# 1_NZPP.net
KiCad netlist of a schematic drawn in Altium Designer
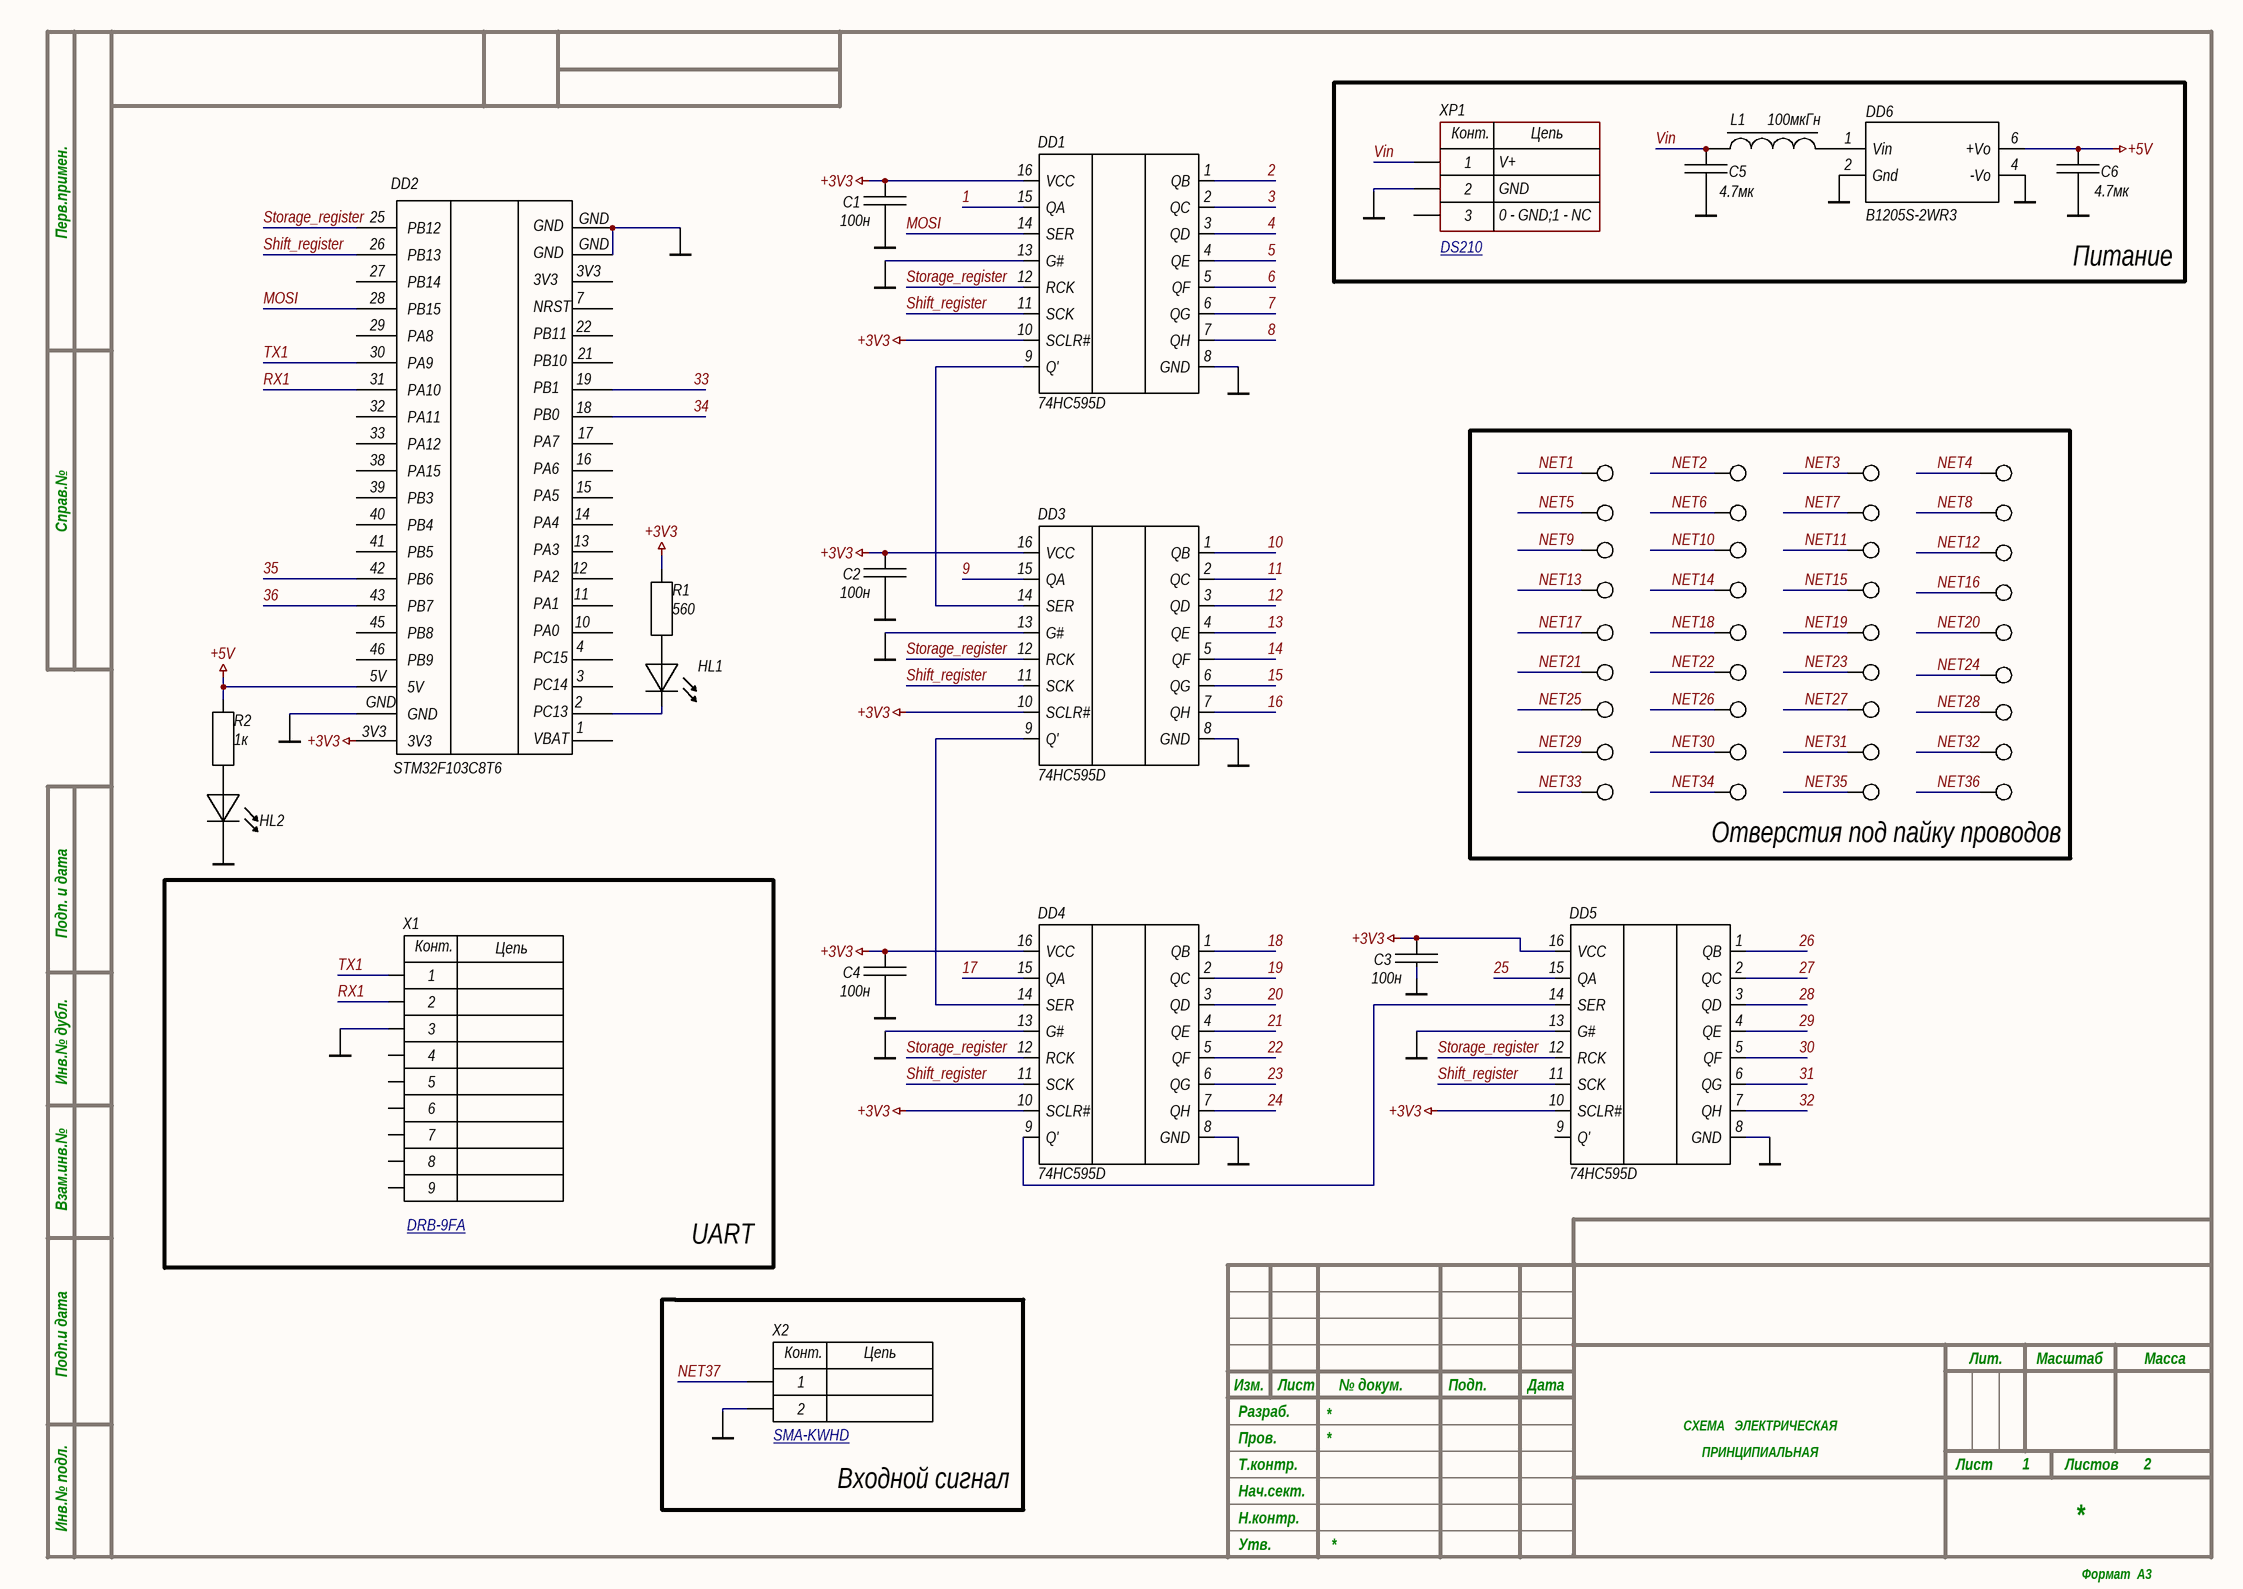
[diagram p0: 1.NZPP.SchDoc]

(export (version "E")
  (design (tool "Eeschema 10.0.6"))
  (components
    (comp (ref "*") (value "Point") (footprint "Point") (libsource (lib "Schlib1") (part "Point")))
    (comp (ref "*1") (value "Point") (footprint "Point") (libsource (lib "Schlib1") (part "Point")))
    (comp (ref "*2") (value "Point") (footprint "Point") (libsource (lib "Schlib1") (part "Point")))
    (comp (ref "*3") (value "Point") (footprint "Point") (libsource (lib "Schlib1") (part "Point")))
    (comp (ref "*4") (value "Point") (footprint "Point") (libsource (lib "Schlib1") (part "Point")))
    (comp (ref "*5") (value "Point") (footprint "Point") (libsource (lib "Schlib1") (part "Point")))
    (comp (ref "*6") (value "Point") (footprint "Point") (libsource (lib "Schlib1") (part "Point")))
    (comp (ref "*7") (value "Point") (footprint "Point") (libsource (lib "Schlib1") (part "Point")))
    (comp (ref "*8") (value "Point") (footprint "Point") (libsource (lib "Schlib1") (part "Point")))
    (comp (ref "*9") (value "Point") (footprint "Point") (libsource (lib "Schlib1") (part "Point")))
    (comp (ref "*10") (value "Point") (footprint "Point") (libsource (lib "Schlib1") (part "Point")))
    (comp (ref "*11") (value "Point") (footprint "Point") (libsource (lib "Schlib1") (part "Point")))
    (comp (ref "*12") (value "Point") (footprint "Point") (libsource (lib "Schlib1") (part "Point")))
    (comp (ref "*13") (value "Point") (footprint "Point") (libsource (lib "Schlib1") (part "Point")))
    (comp (ref "*14") (value "Point") (footprint "Point") (libsource (lib "Schlib1") (part "Point")))
    (comp (ref "*15") (value "Point") (footprint "Point") (libsource (lib "Schlib1") (part "Point")))
    (comp (ref "*16") (value "Point") (footprint "Point") (libsource (lib "Schlib1") (part "Point")))
    (comp (ref "*17") (value "Point") (footprint "Point") (libsource (lib "Schlib1") (part "Point")))
    (comp (ref "*18") (value "Point") (footprint "Point") (libsource (lib "Schlib1") (part "Point")))
    (comp (ref "*19") (value "Point") (footprint "Point") (libsource (lib "Schlib1") (part "Point")))
    (comp (ref "*20") (value "Point") (footprint "Point") (libsource (lib "Schlib1") (part "Point")))
    (comp (ref "*21") (value "Point") (footprint "Point") (libsource (lib "Schlib1") (part "Point")))
    (comp (ref "*22") (value "Point") (footprint "Point") (libsource (lib "Schlib1") (part "Point")))
    (comp (ref "*23") (value "Point") (footprint "Point") (libsource (lib "Schlib1") (part "Point")))
    (comp (ref "*24") (value "Point") (footprint "Point") (libsource (lib "Schlib1") (part "Point")))
    (comp (ref "*25") (value "Point") (footprint "Point") (libsource (lib "Schlib1") (part "Point")))
    (comp (ref "*26") (value "Point") (footprint "Point") (libsource (lib "Schlib1") (part "Point")))
    (comp (ref "*27") (value "Point") (footprint "Point") (libsource (lib "Schlib1") (part "Point")))
    (comp (ref "*28") (value "Point") (footprint "Point") (libsource (lib "Schlib1") (part "Point")))
    (comp (ref "*29") (value "Point") (footprint "Point") (libsource (lib "Schlib1") (part "Point")))
    (comp (ref "*30") (value "Point") (footprint "Point") (libsource (lib "Schlib1") (part "Point")))
    (comp (ref "*31") (value "Point") (footprint "Point") (libsource (lib "Schlib1") (part "Point")))
    (comp (ref "*32") (value "Point") (footprint "Point") (libsource (lib "Schlib1") (part "Point")))
    (comp (ref "*33") (value "Point") (footprint "Point") (libsource (lib "Schlib1") (part "Point")))
    (comp (ref "*34") (value "Point") (footprint "Point") (libsource (lib "Schlib1") (part "Point")))
    (comp (ref "*35") (value "Point") (footprint "Point") (libsource (lib "Schlib1") (part "Point")))
    (comp (ref "C1")
      (value "100н")
      (footprint "CAP: 0805")
      (libsource (lib "capacitor") (part "Ceramic_0805"))
    )
    (comp (ref "C2")
      (value "100н")
      (footprint "CAP: 0805")
      (libsource (lib "capacitor") (part "Ceramic_0805"))
    )
    (comp (ref "C3")
      (value "100н")
      (footprint "CAP: 0805")
      (libsource (lib "capacitor") (part "Ceramic_0805"))
    )
    (comp (ref "C4")
      (value "100н")
      (footprint "CAP: 0805")
      (libsource (lib "capacitor") (part "Ceramic_0805"))
    )
    (comp (ref "C5")
      (value "4.7мк")
      (footprint "CAP: 0805")
      (libsource (lib "capacitor") (part "Ceramic_0805"))
    )
    (comp (ref "C6")
      (value "4.7мк")
      (footprint "CAP: 0805")
      (libsource (lib "capacitor") (part "Ceramic_0805"))
    )
    (comp (ref "DD1") (value "74HC595D") (footprint "74HC595D") (libsource (lib "Schlib1") (part "74HC595D")))
    (comp (ref "DD2")
      (value "STM32F103C8T6")
      (footprint "STM32F103C8T6 - duplicate")
      (libsource (lib "Schlib1") (part "STM32F103"))
    )
    (comp (ref "DD3") (value "74HC595D") (footprint "74HC595D") (libsource (lib "") (part "74HC595D_1")))
    (comp (ref "DD4") (value "74HC595D") (footprint "74HC595D") (libsource (lib "") (part "74HC595D_1")))
    (comp (ref "DD5") (value "74HC595D") (footprint "74HC595D") (libsource (lib "") (part "74HC595D_1")))
    (comp (ref "DD6")
      (value "B1205S-2WR3")
      (footprint "B1205S-2WR3")
      (libsource (lib "Schlib1") (part "B1205S-2WR3"))
    )
    (comp (ref "HL1") (value "GNL-3012HD") (footprint "led green") (libsource (lib "Schlib1") (part "LED")))
    (comp (ref "HL2") (value "GNL-3012HD") (footprint "led") (libsource (lib "Schlib1") (part "LED")))
    (comp (ref "L1")
      (value "100мкГн")
      (footprint "100мкГн")
      (libsource (lib "Schlib1") (part "Дроссель 100мкГн CD43-101K"))
    )
    (comp (ref "R1")
      (value "560")
      (footprint "RES: 0805")
      (libsource (lib "resistor") (part "Resistor_0805"))
    )
    (comp (ref "R2") (value "1к") (footprint "RES: 0805") (libsource (lib "resistor") (part "Resistor_0805")))
    (comp (ref "X1") (value "DRB-9FA") (footprint "CON: DB-9F") (libsource (lib "Schlib1") (part "DRB-9FA")))
    (comp (ref "X2")
      (value "SMA-KWHD")
      (footprint "CON: SMA-KWHD")
      (libsource (lib "Schlib1") (part "Connector_terminal_2pin"))
    )
    (comp (ref "XP1") (value "DS210") (footprint "CON: DS210") (libsource (lib "Schlib1") (part "DS210")))
  )
  (nets
    (net (code "1") (name "+3V3") (class "Default")
      (node (ref "C1") (pin "2") (pinfunction "2_2") (pintype "passive"))
      (node (ref "C2") (pin "2") (pinfunction "2_2") (pintype "passive"))
      (node (ref "C3") (pin "2") (pinfunction "2_2") (pintype "passive"))
      (node (ref "C4") (pin "2") (pinfunction "2_2") (pintype "passive"))
      (node (ref "DD1") (pin "10") (pinfunction "SCLR#_10") (pintype "passive"))
      (node (ref "DD1") (pin "16") (pinfunction "VCC_16") (pintype "passive"))
      (node (ref "DD2") (pin "A2") (pinfunction "3V3_A2") (pintype "passive"))
      (node (ref "DD3") (pin "10") (pinfunction "SCLR#_10") (pintype "passive"))
      (node (ref "DD3") (pin "16") (pinfunction "VCC_16") (pintype "passive"))
      (node (ref "DD4") (pin "10") (pinfunction "SCLR#_10") (pintype "passive"))
      (node (ref "DD4") (pin "16") (pinfunction "VCC_16") (pintype "passive"))
      (node (ref "DD5") (pin "10") (pinfunction "SCLR#_10") (pintype "passive"))
      (node (ref "DD5") (pin "16") (pinfunction "VCC_16") (pintype "passive"))
      (node (ref "R1") (pin "2") (pinfunction "2_2") (pintype "passive"))
    )
    (net (code "2") (name "+5V") (class "Default")
      (node (ref "C6") (pin "2") (pinfunction "2_2") (pintype "passive"))
      (node (ref "DD2") (pin "5V") (pinfunction "5V_5V") (pintype "passive"))
      (node (ref "DD6") (pin "6") (pinfunction "+Vo_6") (pintype "passive"))
      (node (ref "R2") (pin "2") (pinfunction "2_2") (pintype "passive"))
    )
    (net (code "3") (name "/1") (class "Default")
      (node (ref "DD1") (pin "15") (pinfunction "QA_15") (pintype "passive"))
    )
    (net (code "4") (name "/2") (class "Default")
      (node (ref "DD1") (pin "1") (pinfunction "QB_1") (pintype "passive"))
    )
    (net (code "5") (name "/3") (class "Default")
      (node (ref "DD1") (pin "2") (pinfunction "QC_2") (pintype "passive"))
    )
    (net (code "6") (name "/4") (class "Default")
      (node (ref "DD1") (pin "3") (pinfunction "QD_3") (pintype "passive"))
    )
    (net (code "7") (name "/5") (class "Default")
      (node (ref "DD1") (pin "4") (pinfunction "QE_4") (pintype "passive"))
    )
    (net (code "8") (name "/6") (class "Default")
      (node (ref "DD1") (pin "5") (pinfunction "QF_5") (pintype "passive"))
    )
    (net (code "9") (name "/7") (class "Default")
      (node (ref "DD1") (pin "6") (pinfunction "QG_6") (pintype "passive"))
    )
    (net (code "10") (name "/8") (class "Default")
      (node (ref "DD1") (pin "7") (pinfunction "QH_7") (pintype "passive"))
    )
    (net (code "11") (name "/9") (class "Default")
      (node (ref "DD3") (pin "15") (pinfunction "QA_15") (pintype "passive"))
    )
    (net (code "12") (name "/10") (class "Default")
      (node (ref "DD3") (pin "1") (pinfunction "QB_1") (pintype "passive"))
    )
    (net (code "13") (name "/11") (class "Default")
      (node (ref "DD3") (pin "2") (pinfunction "QC_2") (pintype "passive"))
    )
    (net (code "14") (name "/12") (class "Default")
      (node (ref "DD3") (pin "3") (pinfunction "QD_3") (pintype "passive"))
    )
    (net (code "15") (name "/13") (class "Default")
      (node (ref "DD3") (pin "4") (pinfunction "QE_4") (pintype "passive"))
    )
    (net (code "16") (name "/14") (class "Default")
      (node (ref "DD3") (pin "5") (pinfunction "QF_5") (pintype "passive"))
    )
    (net (code "17") (name "/15") (class "Default")
      (node (ref "DD3") (pin "6") (pinfunction "QG_6") (pintype "passive"))
    )
    (net (code "18") (name "/16") (class "Default")
      (node (ref "DD3") (pin "7") (pinfunction "QH_7") (pintype "passive"))
    )
    (net (code "19") (name "/17") (class "Default")
      (node (ref "DD4") (pin "15") (pinfunction "QA_15") (pintype "passive"))
    )
    (net (code "20") (name "/18") (class "Default")
      (node (ref "DD4") (pin "1") (pinfunction "QB_1") (pintype "passive"))
    )
    (net (code "21") (name "/19") (class "Default")
      (node (ref "DD4") (pin "2") (pinfunction "QC_2") (pintype "passive"))
    )
    (net (code "22") (name "/20") (class "Default")
      (node (ref "DD4") (pin "3") (pinfunction "QD_3") (pintype "passive"))
    )
    (net (code "23") (name "/21") (class "Default")
      (node (ref "DD4") (pin "4") (pinfunction "QE_4") (pintype "passive"))
    )
    (net (code "24") (name "/22") (class "Default")
      (node (ref "DD4") (pin "5") (pinfunction "QF_5") (pintype "passive"))
    )
    (net (code "25") (name "/23") (class "Default")
      (node (ref "DD4") (pin "6") (pinfunction "QG_6") (pintype "passive"))
    )
    (net (code "26") (name "/24") (class "Default")
      (node (ref "DD4") (pin "7") (pinfunction "QH_7") (pintype "passive"))
    )
    (net (code "27") (name "/25") (class "Default")
      (node (ref "DD5") (pin "15") (pinfunction "QA_15") (pintype "passive"))
    )
    (net (code "28") (name "/26") (class "Default")
      (node (ref "DD5") (pin "1") (pinfunction "QB_1") (pintype "passive"))
    )
    (net (code "29") (name "/27") (class "Default")
      (node (ref "DD5") (pin "2") (pinfunction "QC_2") (pintype "passive"))
    )
    (net (code "30") (name "/28") (class "Default")
      (node (ref "DD5") (pin "3") (pinfunction "QD_3") (pintype "passive"))
    )
    (net (code "31") (name "/29") (class "Default")
      (node (ref "DD5") (pin "4") (pinfunction "QE_4") (pintype "passive"))
    )
    (net (code "32") (name "/30") (class "Default")
      (node (ref "DD5") (pin "5") (pinfunction "QF_5") (pintype "passive"))
    )
    (net (code "33") (name "/31") (class "Default")
      (node (ref "DD5") (pin "6") (pinfunction "QG_6") (pintype "passive"))
    )
    (net (code "34") (name "/32") (class "Default")
      (node (ref "DD5") (pin "7") (pinfunction "QH_7") (pintype "passive"))
    )
    (net (code "35") (name "/33") (class "Default")
      (node (ref "DD2") (pin "19") (pinfunction "PB1_19") (pintype "passive"))
    )
    (net (code "36") (name "/34") (class "Default")
      (node (ref "DD2") (pin "18") (pinfunction "PB0_18") (pintype "passive"))
    )
    (net (code "37") (name "/35") (class "Default")
      (node (ref "DD2") (pin "42") (pinfunction "PB6_42") (pintype "passive"))
    )
    (net (code "38") (name "/36") (class "Default")
      (node (ref "DD2") (pin "43") (pinfunction "PB7_43") (pintype "passive"))
    )
    (net (code "39") (name "/MOSI") (class "Default")
      (node (ref "DD1") (pin "14") (pinfunction "SER_14") (pintype "passive"))
      (node (ref "DD2") (pin "28") (pinfunction "PB15_28") (pintype "passive"))
    )
    (net (code "40") (name "/NET1") (class "Default")
      (node (ref "*") (pin "1") (pinfunction "4_1") (pintype "passive"))
    )
    (net (code "41") (name "/NET2") (class "Default")
      (node (ref "*1") (pin "1") (pinfunction "4_1") (pintype "passive"))
    )
    (net (code "42") (name "/NET3") (class "Default")
      (node (ref "*2") (pin "1") (pinfunction "4_1") (pintype "passive"))
    )
    (net (code "43") (name "/NET4") (class "Default")
      (node (ref "*3") (pin "1") (pinfunction "4_1") (pintype "passive"))
    )
    (net (code "44") (name "/NET5") (class "Default")
      (node (ref "*4") (pin "1") (pinfunction "4_1") (pintype "passive"))
    )
    (net (code "45") (name "/NET6") (class "Default")
      (node (ref "*5") (pin "1") (pinfunction "4_1") (pintype "passive"))
    )
    (net (code "46") (name "/NET7") (class "Default")
      (node (ref "*6") (pin "1") (pinfunction "4_1") (pintype "passive"))
    )
    (net (code "47") (name "/NET8") (class "Default")
      (node (ref "*7") (pin "1") (pinfunction "4_1") (pintype "passive"))
    )
    (net (code "48") (name "/NET9") (class "Default")
      (node (ref "*8") (pin "1") (pinfunction "4_1") (pintype "passive"))
    )
    (net (code "49") (name "/NET10") (class "Default")
      (node (ref "*9") (pin "1") (pinfunction "4_1") (pintype "passive"))
    )
    (net (code "50") (name "/NET11") (class "Default")
      (node (ref "*10") (pin "1") (pinfunction "4_1") (pintype "passive"))
    )
    (net (code "51") (name "/NET12") (class "Default")
      (node (ref "*11") (pin "1") (pinfunction "4_1") (pintype "passive"))
    )
    (net (code "52") (name "/NET13") (class "Default")
      (node (ref "*12") (pin "1") (pinfunction "4_1") (pintype "passive"))
    )
    (net (code "53") (name "/NET14") (class "Default")
      (node (ref "*13") (pin "1") (pinfunction "4_1") (pintype "passive"))
    )
    (net (code "54") (name "/NET15") (class "Default")
      (node (ref "*14") (pin "1") (pinfunction "4_1") (pintype "passive"))
    )
    (net (code "55") (name "/NET16") (class "Default")
      (node (ref "*15") (pin "1") (pinfunction "4_1") (pintype "passive"))
    )
    (net (code "56") (name "/NET17") (class "Default")
      (node (ref "*16") (pin "1") (pinfunction "4_1") (pintype "passive"))
    )
    (net (code "57") (name "/NET18") (class "Default")
      (node (ref "*17") (pin "1") (pinfunction "4_1") (pintype "passive"))
    )
    (net (code "58") (name "/NET19") (class "Default")
      (node (ref "*18") (pin "1") (pinfunction "4_1") (pintype "passive"))
    )
    (net (code "59") (name "/NET20") (class "Default")
      (node (ref "*19") (pin "1") (pinfunction "4_1") (pintype "passive"))
    )
    (net (code "60") (name "/NET21") (class "Default")
      (node (ref "*20") (pin "1") (pinfunction "4_1") (pintype "passive"))
    )
    (net (code "61") (name "/NET22") (class "Default")
      (node (ref "*21") (pin "1") (pinfunction "4_1") (pintype "passive"))
    )
    (net (code "62") (name "/NET23") (class "Default")
      (node (ref "*22") (pin "1") (pinfunction "4_1") (pintype "passive"))
    )
    (net (code "63") (name "/NET24") (class "Default")
      (node (ref "*23") (pin "1") (pinfunction "4_1") (pintype "passive"))
    )
    (net (code "64") (name "/NET25") (class "Default")
      (node (ref "*24") (pin "1") (pinfunction "4_1") (pintype "passive"))
    )
    (net (code "65") (name "/NET26") (class "Default")
      (node (ref "*25") (pin "1") (pinfunction "4_1") (pintype "passive"))
    )
    (net (code "66") (name "/NET27") (class "Default")
      (node (ref "*26") (pin "1") (pinfunction "4_1") (pintype "passive"))
    )
    (net (code "67") (name "/NET28") (class "Default")
      (node (ref "*27") (pin "1") (pinfunction "4_1") (pintype "passive"))
    )
    (net (code "68") (name "/NET29") (class "Default")
      (node (ref "*28") (pin "1") (pinfunction "4_1") (pintype "passive"))
    )
    (net (code "69") (name "/NET30") (class "Default")
      (node (ref "*29") (pin "1") (pinfunction "4_1") (pintype "passive"))
    )
    (net (code "70") (name "/NET31") (class "Default")
      (node (ref "*30") (pin "1") (pinfunction "4_1") (pintype "passive"))
    )
    (net (code "71") (name "/NET32") (class "Default")
      (node (ref "*31") (pin "1") (pinfunction "4_1") (pintype "passive"))
    )
    (net (code "72") (name "/NET33") (class "Default")
      (node (ref "*32") (pin "1") (pinfunction "4_1") (pintype "passive"))
    )
    (net (code "73") (name "/NET34") (class "Default")
      (node (ref "*33") (pin "1") (pinfunction "4_1") (pintype "passive"))
    )
    (net (code "74") (name "/NET35") (class "Default")
      (node (ref "*34") (pin "1") (pinfunction "4_1") (pintype "passive"))
    )
    (net (code "75") (name "/NET36") (class "Default")
      (node (ref "*35") (pin "1") (pinfunction "4_1") (pintype "passive"))
    )
    (net (code "76") (name "/NET37") (class "Default")
      (node (ref "X2") (pin "1") (pinfunction "1_1") (pintype "passive"))
    )
    (net (code "77") (name "/RX1") (class "Default")
      (node (ref "DD2") (pin "31") (pinfunction "PA10_31") (pintype "passive"))
      (node (ref "X1") (pin "2") (pinfunction "2_2") (pintype "passive"))
    )
    (net (code "78") (name "/Shift_register") (class "Default")
      (node (ref "DD1") (pin "11") (pinfunction "SCK_11") (pintype "passive"))
      (node (ref "DD2") (pin "26") (pinfunction "PB13_26") (pintype "passive"))
      (node (ref "DD3") (pin "11") (pinfunction "SCK_11") (pintype "passive"))
      (node (ref "DD4") (pin "11") (pinfunction "SCK_11") (pintype "passive"))
      (node (ref "DD5") (pin "11") (pinfunction "SCK_11") (pintype "passive"))
    )
    (net (code "79") (name "/Storage_register") (class "Default")
      (node (ref "DD1") (pin "12") (pinfunction "RCK_12") (pintype "passive"))
      (node (ref "DD2") (pin "25") (pinfunction "PB12_25") (pintype "passive"))
      (node (ref "DD3") (pin "12") (pinfunction "RCK_12") (pintype "passive"))
      (node (ref "DD4") (pin "12") (pinfunction "RCK_12") (pintype "passive"))
      (node (ref "DD5") (pin "12") (pinfunction "RCK_12") (pintype "passive"))
    )
    (net (code "80") (name "/TX1") (class "Default")
      (node (ref "DD2") (pin "30") (pinfunction "PA9_30") (pintype "passive"))
      (node (ref "X1") (pin "1") (pinfunction "1_1") (pintype "passive"))
    )
    (net (code "81") (name "/Vin") (class "Default")
      (node (ref "C5") (pin "2") (pinfunction "2_2") (pintype "passive"))
      (node (ref "L1") (pin "1") (pinfunction "1_1") (pintype "passive"))
      (node (ref "XP1") (pin "1") (pinfunction "1_1") (pintype "passive"))
    )
    (net (code "82") (name "GND") (class "Default")
      (node (ref "C1") (pin "1") (pinfunction "1_1") (pintype "passive"))
      (node (ref "C2") (pin "1") (pinfunction "1_1") (pintype "passive"))
      (node (ref "C3") (pin "1") (pinfunction "1_1") (pintype "passive"))
      (node (ref "C4") (pin "1") (pinfunction "1_1") (pintype "passive"))
      (node (ref "C5") (pin "1") (pinfunction "1_1") (pintype "passive"))
      (node (ref "C6") (pin "1") (pinfunction "1_1") (pintype "passive"))
      (node (ref "DD1") (pin "13") (pinfunction "G#_13") (pintype "passive"))
      (node (ref "DD1") (pin "8") (pinfunction "GND_8") (pintype "passive"))
      (node (ref "DD2") (pin "GND") (pinfunction "GND_GND") (pintype "passive"))
      (node (ref "DD3") (pin "13") (pinfunction "G#_13") (pintype "passive"))
      (node (ref "DD3") (pin "8") (pinfunction "GND_8") (pintype "passive"))
      (node (ref "DD4") (pin "13") (pinfunction "G#_13") (pintype "passive"))
      (node (ref "DD4") (pin "8") (pinfunction "GND_8") (pintype "passive"))
      (node (ref "DD5") (pin "13") (pinfunction "G#_13") (pintype "passive"))
      (node (ref "DD5") (pin "8") (pinfunction "GND_8") (pintype "passive"))
      (node (ref "DD6") (pin "2") (pinfunction "Gnd_2") (pintype "passive"))
      (node (ref "DD6") (pin "4") (pinfunction "-Vo_4") (pintype "passive"))
      (node (ref "HL2") (pin "2") (pinfunction "C_2") (pintype "passive"))
      (node (ref "X1") (pin "3") (pinfunction "3_3") (pintype "power_in"))
      (node (ref "X2") (pin "2") (pinfunction "2_2") (pintype "passive"))
      (node (ref "XP1") (pin "2") (pinfunction "2_2") (pintype "passive"))
    )
    (net (code "83") (name "Net-(DD1-Q')") (class "Default")
      (node (ref "DD1") (pin "9") (pinfunction "Q'_9") (pintype "passive"))
      (node (ref "DD3") (pin "14") (pinfunction "SER_14") (pintype "passive"))
    )
    (net (code "84") (name "Net-(DD2-PC13)") (class "Default")
      (node (ref "DD2") (pin "2") (pinfunction "PC13_2") (pintype "passive"))
      (node (ref "HL1") (pin "2") (pinfunction "C_2") (pintype "passive"))
    )
    (net (code "85") (name "Net-(DD3-Q')") (class "Default")
      (node (ref "DD3") (pin "9") (pinfunction "Q'_9") (pintype "passive"))
      (node (ref "DD4") (pin "14") (pinfunction "SER_14") (pintype "passive"))
    )
    (net (code "86") (name "Net-(DD4-Q')") (class "Default")
      (node (ref "DD4") (pin "9") (pinfunction "Q'_9") (pintype "passive"))
      (node (ref "DD5") (pin "14") (pinfunction "SER_14") (pintype "passive"))
    )
    (net (code "87") (name "Net-(DD6-Vin)") (class "Default")
      (node (ref "DD6") (pin "1") (pinfunction "Vin_1") (pintype "passive"))
      (node (ref "L1") (pin "2") (pinfunction "2_2") (pintype "passive"))
    )
    (net (code "88") (name "Net-(HL1-A)") (class "Default")
      (node (ref "HL1") (pin "1") (pinfunction "A_1") (pintype "passive"))
      (node (ref "R1") (pin "1") (pinfunction "1_1") (pintype "passive"))
    )
    (net (code "89") (name "Net-(HL2-A)") (class "Default")
      (node (ref "HL2") (pin "1") (pinfunction "A_1") (pintype "passive"))
      (node (ref "R2") (pin "1") (pinfunction "1_1") (pintype "passive"))
    )
    (net (code "90") (name "unconnected-(DD2-3V3-PadA1)") (class "Default")
      (node (ref "DD2") (pin "A1") (pinfunction "3V3_A1") (pintype "passive"))
    )
    (net (code "91") (name "unconnected-(DD2-NRST-Pad7)") (class "Default")
      (node (ref "DD2") (pin "7") (pinfunction "NRST_7") (pintype "passive"))
    )
    (net (code "92") (name "unconnected-(DD2-PA0-Pad10)") (class "Default")
      (node (ref "DD2") (pin "10") (pinfunction "PA0_10") (pintype "passive"))
    )
    (net (code "93") (name "unconnected-(DD2-PA1-Pad11)") (class "Default")
      (node (ref "DD2") (pin "11") (pinfunction "PA1_11") (pintype "passive"))
    )
    (net (code "94") (name "unconnected-(DD2-PA2-Pad12)") (class "Default")
      (node (ref "DD2") (pin "12") (pinfunction "PA2_12") (pintype "passive"))
    )
    (net (code "95") (name "unconnected-(DD2-PA3-Pad13)") (class "Default")
      (node (ref "DD2") (pin "13") (pinfunction "PA3_13") (pintype "passive"))
    )
    (net (code "96") (name "unconnected-(DD2-PA4-Pad14)") (class "Default")
      (node (ref "DD2") (pin "14") (pinfunction "PA4_14") (pintype "passive"))
    )
    (net (code "97") (name "unconnected-(DD2-PA5-Pad15)") (class "Default")
      (node (ref "DD2") (pin "15") (pinfunction "PA5_15") (pintype "passive"))
    )
    (net (code "98") (name "unconnected-(DD2-PA6-Pad16)") (class "Default")
      (node (ref "DD2") (pin "16") (pinfunction "PA6_16") (pintype "passive"))
    )
    (net (code "99") (name "unconnected-(DD2-PA7-Pad17)") (class "Default")
      (node (ref "DD2") (pin "17") (pinfunction "PA7_17") (pintype "passive"))
    )
    (net (code "100") (name "unconnected-(DD2-PA8-Pad29)") (class "Default")
      (node (ref "DD2") (pin "29") (pinfunction "PA8_29") (pintype "passive"))
    )
    (net (code "101") (name "unconnected-(DD2-PA11-Pad32)") (class "Default")
      (node (ref "DD2") (pin "32") (pinfunction "PA11_32") (pintype "passive"))
    )
    (net (code "102") (name "unconnected-(DD2-PA12-Pad33)") (class "Default")
      (node (ref "DD2") (pin "33") (pinfunction "PA12_33") (pintype "passive"))
    )
    (net (code "103") (name "unconnected-(DD2-PA15-Pad38)") (class "Default")
      (node (ref "DD2") (pin "38") (pinfunction "PA15_38") (pintype "passive"))
    )
    (net (code "104") (name "unconnected-(DD2-PB3-Pad39)") (class "Default")
      (node (ref "DD2") (pin "39") (pinfunction "PB3_39") (pintype "passive"))
    )
    (net (code "105") (name "unconnected-(DD2-PB4-Pad40)") (class "Default")
      (node (ref "DD2") (pin "40") (pinfunction "PB4_40") (pintype "passive"))
    )
    (net (code "106") (name "unconnected-(DD2-PB5-Pad41)") (class "Default")
      (node (ref "DD2") (pin "41") (pinfunction "PB5_41") (pintype "passive"))
    )
    (net (code "107") (name "unconnected-(DD2-PB8-Pad45)") (class "Default")
      (node (ref "DD2") (pin "45") (pinfunction "PB8_45") (pintype "passive"))
    )
    (net (code "108") (name "unconnected-(DD2-PB9-Pad46)") (class "Default")
      (node (ref "DD2") (pin "46") (pinfunction "PB9_46") (pintype "passive"))
    )
    (net (code "109") (name "unconnected-(DD2-PB10-Pad21)") (class "Default")
      (node (ref "DD2") (pin "21") (pinfunction "PB10_21") (pintype "passive"))
    )
    (net (code "110") (name "unconnected-(DD2-PB11-Pad22)") (class "Default")
      (node (ref "DD2") (pin "22") (pinfunction "PB11_22") (pintype "passive"))
    )
    (net (code "111") (name "unconnected-(DD2-PB14-Pad27)") (class "Default")
      (node (ref "DD2") (pin "27") (pinfunction "PB14_27") (pintype "passive"))
    )
    (net (code "112") (name "unconnected-(DD2-PC14-Pad3)") (class "Default")
      (node (ref "DD2") (pin "3") (pinfunction "PC14_3") (pintype "passive"))
    )
    (net (code "113") (name "unconnected-(DD2-PC15-Pad4)") (class "Default")
      (node (ref "DD2") (pin "4") (pinfunction "PC15_4") (pintype "passive"))
    )
    (net (code "114") (name "unconnected-(DD2-Vbat-Pad1)") (class "Default")
      (node (ref "DD2") (pin "1") (pinfunction "Vbat_1") (pintype "passive"))
    )
    (net (code "115") (name "unconnected-(DD5-Q'-Pad9)") (class "Default")
      (node (ref "DD5") (pin "9") (pinfunction "Q'_9") (pintype "passive"))
    )
    (net (code "116") (name "unconnected-(X1-Pad4)") (class "Default")
      (node (ref "X1") (pin "4") (pinfunction "4_4") (pintype "power_in"))
    )
    (net (code "117") (name "unconnected-(X1-Pad5)") (class "Default")
      (node (ref "X1") (pin "5") (pinfunction "5_5") (pintype "power_in"))
    )
    (net (code "118") (name "unconnected-(X1-Pad6)") (class "Default")
      (node (ref "X1") (pin "6") (pinfunction "6_6") (pintype "power_in"))
    )
    (net (code "119") (name "unconnected-(X1-Pad7)") (class "Default")
      (node (ref "X1") (pin "7") (pinfunction "7_7") (pintype "power_in"))
    )
    (net (code "120") (name "unconnected-(X1-Pad8)") (class "Default")
      (node (ref "X1") (pin "8") (pinfunction "8_8") (pintype "power_in"))
    )
    (net (code "121") (name "unconnected-(X1-Pad9)") (class "Default")
      (node (ref "X1") (pin "9") (pinfunction "9_9") (pintype "power_in"))
    )
    (net (code "122") (name "unconnected-(XP1-Pad3)") (class "Default")
      (node (ref "XP1") (pin "3") (pinfunction "3_3") (pintype "passive"))
    )
  )
)
